# LPmini-Prototype_1_1.net
KiCad netlist of a schematic drawn in EAGLE
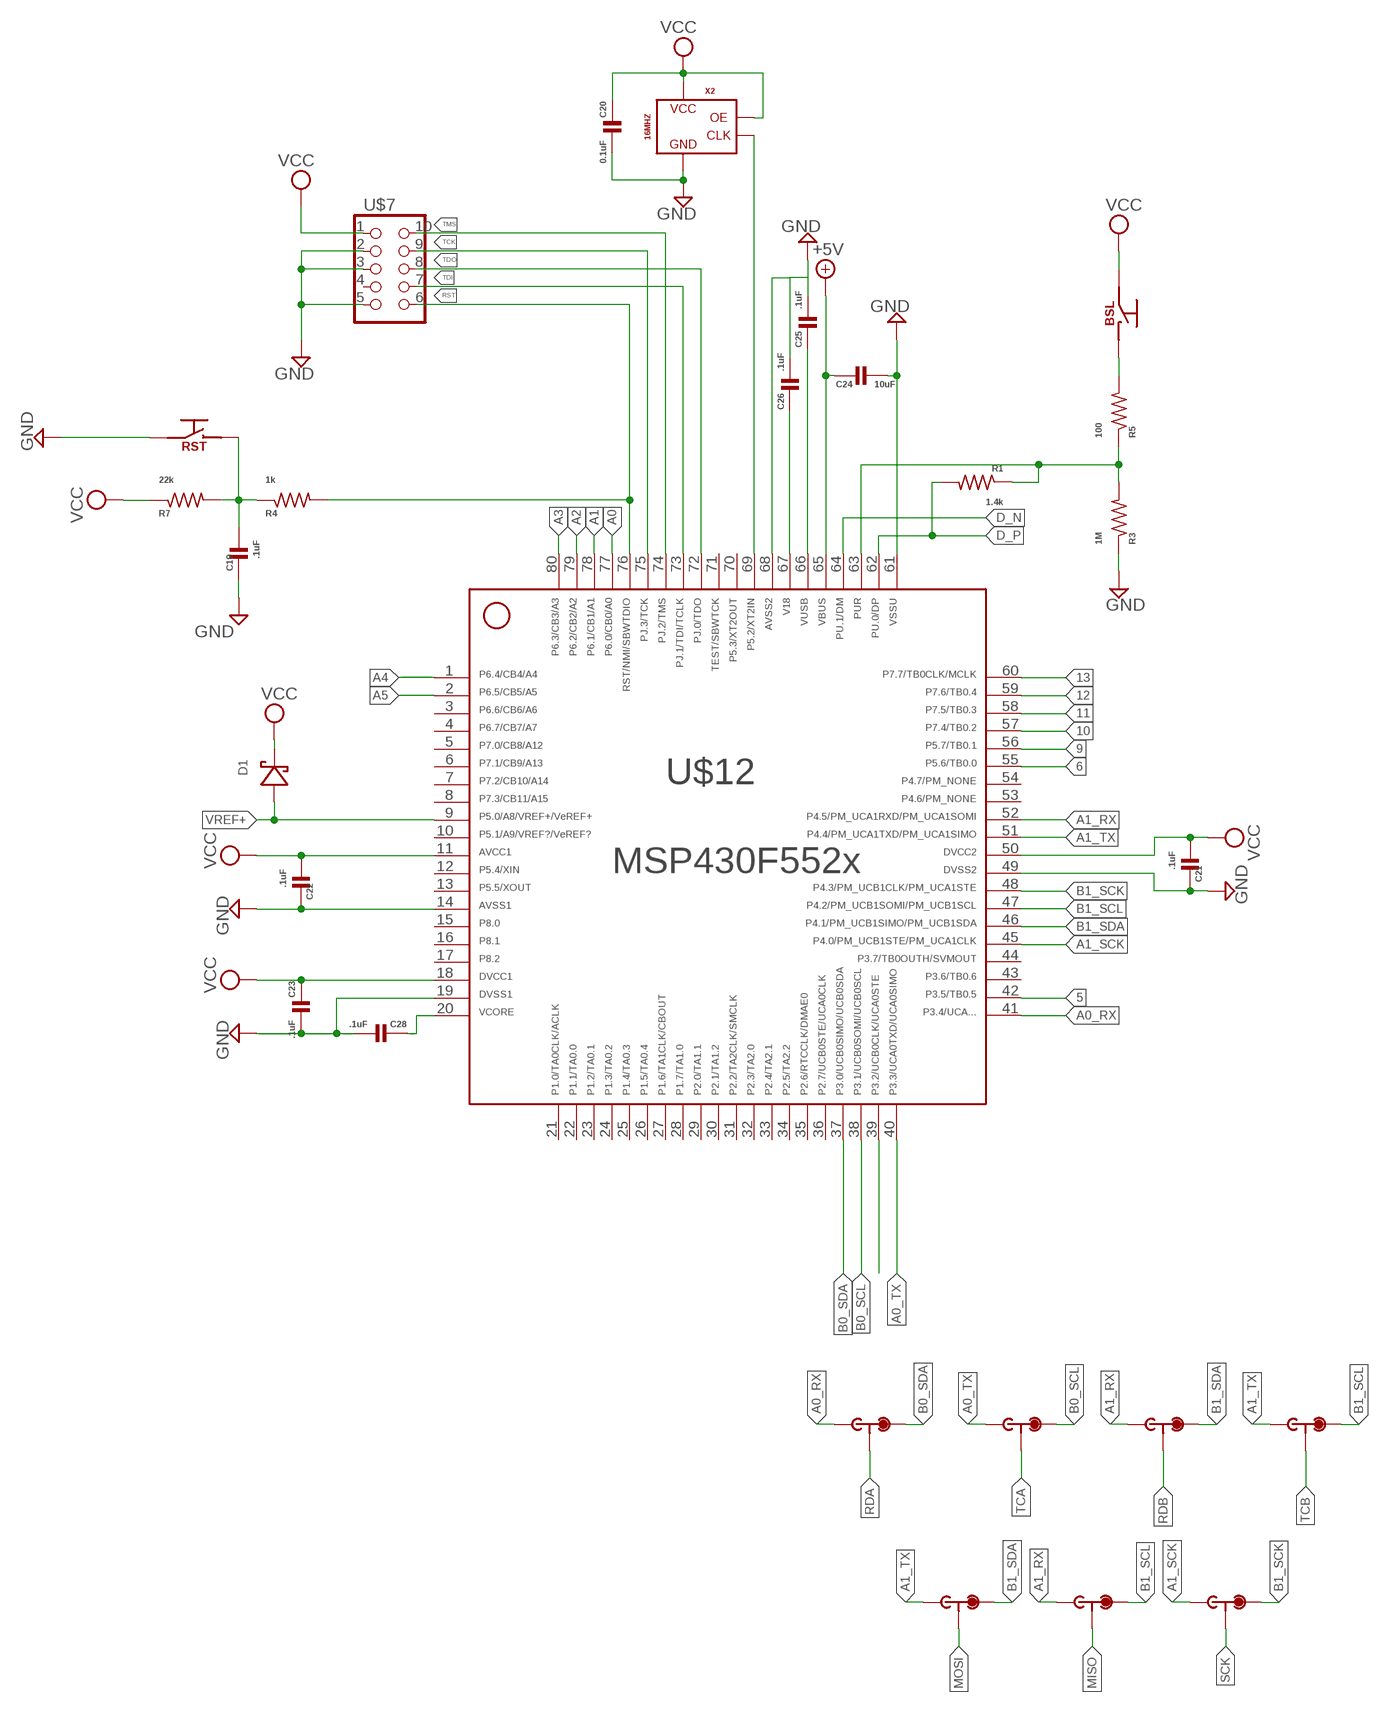
[diagram p0: schematic, sheet 1, part 1 of 2]
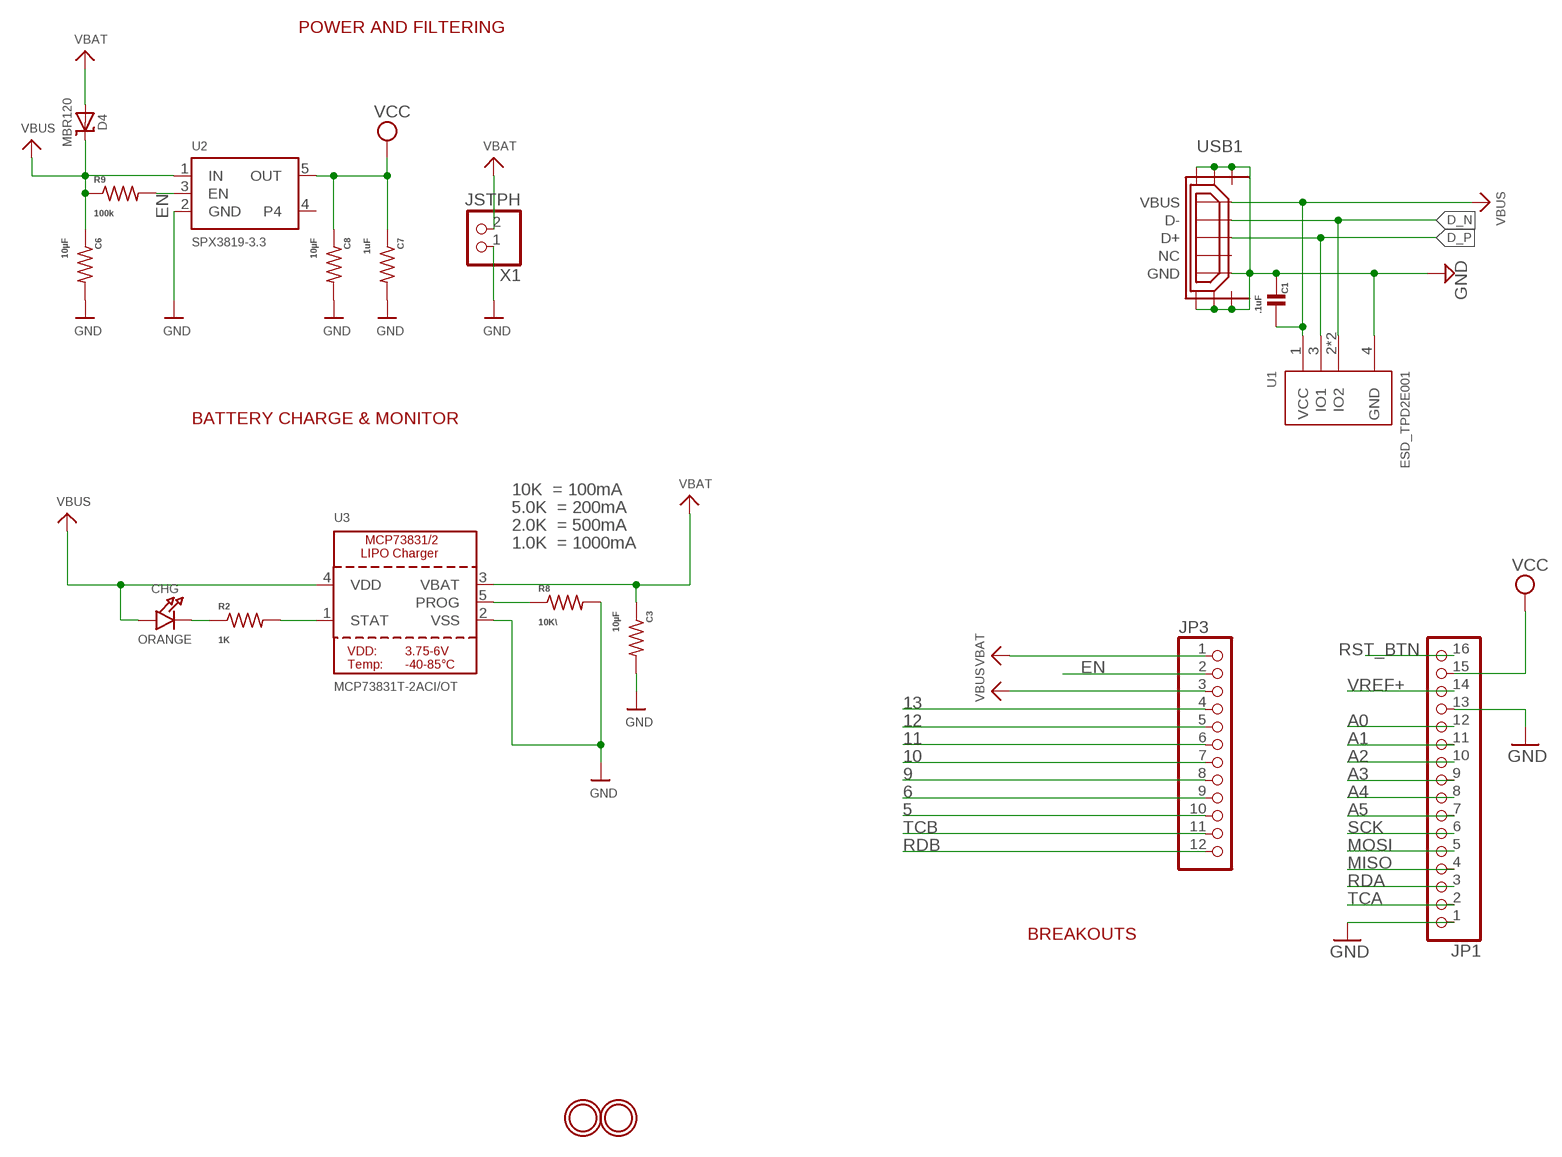
[diagram p1: schematic, sheet 1, part 2 of 2]

(export (version "E")
  (design (tool "Eeschema 10.0.6"))
  (components
    (comp (ref "BSL")
      (value "PB_SMALL_SMD")
      (footprint "eagle-import:PB_KMR2")
      (libsource (lib "eagle-import") (part "PB_SMALL_SMD"))
    )
    (comp (ref "C1")
      (value ".1uF")
      (footprint "eagle-import:C0402")
      (libsource (lib "eagle-import") (part "C-EUC0402"))
    )
    (comp (ref "C3")
      (value "10µF")
      (footprint "eagle-import:R0603")
      (libsource (lib "eagle-import") (part "R-US_R0603"))
    )
    (comp (ref "C6")
      (value "10µF")
      (footprint "eagle-import:R0603")
      (libsource (lib "eagle-import") (part "R-US_R0603"))
    )
    (comp (ref "C7")
      (value "1uF")
      (footprint "eagle-import:R0402")
      (libsource (lib "eagle-import") (part "R-US_R0402"))
    )
    (comp (ref "C8")
      (value "10µF")
      (footprint "eagle-import:R0603")
      (libsource (lib "eagle-import") (part "R-US_R0603"))
    )
    (comp (ref "C19")
      (value ".1uF")
      (footprint "eagle-import:C0402")
      (libsource (lib "eagle-import") (part "C-EUC0402"))
    )
    (comp (ref "C20")
      (value "0.1uF")
      (footprint "eagle-import:C0402")
      (libsource (lib "eagle-import") (part "C-EUC0402"))
    )
    (comp (ref "C21")
      (value ".1uF")
      (footprint "eagle-import:C0402")
      (libsource (lib "eagle-import") (part "C-EUC0402"))
    )
    (comp (ref "C22")
      (value ".1uF")
      (footprint "eagle-import:C0402")
      (libsource (lib "eagle-import") (part "C-EUC0402"))
    )
    (comp (ref "C23")
      (value ".1uF")
      (footprint "eagle-import:C0402")
      (libsource (lib "eagle-import") (part "C-EUC0402"))
    )
    (comp (ref "C24")
      (value "10uF")
      (footprint "eagle-import:C0603")
      (libsource (lib "eagle-import") (part "C-EUC0603"))
    )
    (comp (ref "C25")
      (value ".1uF")
      (footprint "eagle-import:C0402")
      (libsource (lib "eagle-import") (part "C-EUC0402"))
    )
    (comp (ref "C26")
      (value ".1uF")
      (footprint "eagle-import:C0402")
      (libsource (lib "eagle-import") (part "C-EUC0402"))
    )
    (comp (ref "C28")
      (value ".1uF")
      (footprint "eagle-import:C0402")
      (libsource (lib "eagle-import") (part "C-EUC0402"))
    )
    (comp (ref "CHG")
      (value "ORANGE")
      (footprint "eagle-import:CHIPLED_0805_NOOUTLINE")
      (libsource (lib "eagle-import") (part "LED0805_NOOUTLINE"))
    )
    (comp (ref "D1")
      (value "0_JOSEPH_SDIODE0603")
      (footprint "eagle-import:0_JOSEPH_D0603")
      (libsource (lib "eagle-import") (part "0_JOSEPH_SDIODE0603"))
    )
    (comp (ref "D4")
      (value "MBR120")
      (footprint "eagle-import:SOD-123")
      (libsource (lib "eagle-import") (part "DIODE-SCHOTTKYSOD-123"))
    )
    (comp (ref "JP1")
      (value "HEADER-1X16ROUND")
      (footprint "eagle-import:1X16_ROUND")
      (libsource (lib "eagle-import") (part "HEADER-1X16ROUND"))
    )
    (comp (ref "JP3")
      (value "HEADER-1X12")
      (footprint "eagle-import:1X12_ROUND")
      (libsource (lib "eagle-import") (part "HEADER-1X12"))
    )
    (comp (ref "R1")
      (value "1.4k")
      (footprint "eagle-import:R0402")
      (libsource (lib "eagle-import") (part "R-US_R0402"))
    )
    (comp (ref "R2")
      (value "1K")
      (footprint "eagle-import:R0402")
      (libsource (lib "eagle-import") (part "R-US_R0402"))
    )
    (comp (ref "R3")
      (value "1M")
      (footprint "eagle-import:R0402")
      (libsource (lib "eagle-import") (part "R-US_R0402"))
    )
    (comp (ref "R4")
      (value "1k")
      (footprint "eagle-import:R0402")
      (libsource (lib "eagle-import") (part "R-US_R0402"))
    )
    (comp (ref "R5")
      (value "100")
      (footprint "eagle-import:R0402")
      (libsource (lib "eagle-import") (part "R-US_R0402"))
    )
    (comp (ref "R7")
      (value "22k")
      (footprint "eagle-import:R0402")
      (libsource (lib "eagle-import") (part "R-US_R0402"))
    )
    (comp (ref "R8")
      (value "10K\\")
      (footprint "eagle-import:R0402")
      (libsource (lib "eagle-import") (part "R-US_R0402"))
    )
    (comp (ref "R9")
      (value "100k")
      (footprint "eagle-import:R0402")
      (libsource (lib "eagle-import") (part "R-US_R0402"))
    )
    (comp (ref "RST")
      (value "PB_SMALL_SMD")
      (footprint "eagle-import:PB_KMR2")
      (libsource (lib "eagle-import") (part "PB_SMALL_SMD"))
    )
    (comp (ref "U$2")
      (value "3PT_SOLDER_JUMPER")
      (footprint "eagle-import:SOLDER_JUMPER_3")
      (libsource (lib "eagle-import") (part "3PT_SOLDER_JUMPER"))
    )
    (comp (ref "U$4")
      (value "3PT_SOLDER_JUMPER")
      (footprint "eagle-import:SOLDER_JUMPER_3")
      (libsource (lib "eagle-import") (part "3PT_SOLDER_JUMPER"))
    )
    (comp (ref "U$5")
      (value "3PT_SOLDER_JUMPER")
      (footprint "eagle-import:SOLDER_JUMPER_3")
      (libsource (lib "eagle-import") (part "3PT_SOLDER_JUMPER"))
    )
    (comp (ref "U$6")
      (value "3PT_SOLDER_JUMPER")
      (footprint "eagle-import:SOLDER_JUMPER_3")
      (libsource (lib "eagle-import") (part "3PT_SOLDER_JUMPER"))
    )
    (comp (ref "U$7")
      (value "PINHD_2X05SMD")
      (footprint "eagle-import:2X05-SMALL_SMD")
      (libsource (lib "eagle-import") (part "PINHD_2X05SMD"))
    )
    (comp (ref "U$8")
      (value "3PT_SOLDER_JUMPER")
      (footprint "eagle-import:SOLDER_JUMPER_3")
      (libsource (lib "eagle-import") (part "3PT_SOLDER_JUMPER"))
    )
    (comp (ref "U$9")
      (value "3PT_SOLDER_JUMPER")
      (footprint "eagle-import:SOLDER_JUMPER_3")
      (libsource (lib "eagle-import") (part "3PT_SOLDER_JUMPER"))
    )
    (comp (ref "U$10")
      (value "3PT_SOLDER_JUMPER")
      (footprint "eagle-import:SOLDER_JUMPER_3")
      (libsource (lib "eagle-import") (part "3PT_SOLDER_JUMPER"))
    )
    (comp (ref "U$12")
      (value "TI_MSP430_V16_INTERN_F552X---PN80")
      (footprint "eagle-import:TI_MSP430_V16_INTERN_PN80")
      (libsource (lib "eagle-import") (part "TI_MSP430_V16_INTERN_F552X---PN80"))
    )
    (comp (ref "U$31")
      (value "MOUNTINGHOLE2.5")
      (footprint "eagle-import:MOUNTINGHOLE_2.5_PLATED")
      (libsource (lib "eagle-import") (part "MOUNTINGHOLE2.5"))
    )
    (comp (ref "U$32")
      (value "MOUNTINGHOLE2.5")
      (footprint "eagle-import:MOUNTINGHOLE_2.5_PLATED")
      (libsource (lib "eagle-import") (part "MOUNTINGHOLE2.5"))
    )
    (comp (ref "U1")
      (value "ESD_TPD2E001")
      (footprint "eagle-import:PROJECT7264_TPD2E001-DRL")
      (libsource (lib "eagle-import") (part "ESD_TPD2E001"))
    )
    (comp (ref "U2")
      (value "SPX3819-3.3")
      (footprint "eagle-import:SOT23-5")
      (libsource (lib "eagle-import") (part "VREG_SOT23-5"))
    )
    (comp (ref "U3")
      (value "MCP73831T-2ACI/OT")
      (footprint "eagle-import:SOT23-5")
      (libsource (lib "eagle-import") (part "MCP73831/2"))
    )
    (comp (ref "USB1")
      (value "USB_CON-UPDATE_USB_MICRO_FLIPPED")
      (footprint "eagle-import:USB_CON-UPDATE_HIROSE-ZX62R-B-5P")
      (libsource (lib "eagle-import") (part "USB_CON-UPDATE_USB_MICRO_FLIPPED"))
    )
    (comp (ref "X1")
      (value "JSTPH")
      (footprint "eagle-import:JSTPH2")
      (libsource (lib "eagle-import") (part "CON_JST_PH_2PIN"))
    )
    (comp (ref "X2")
      (value "16MHZ")
      (footprint "eagle-import:SMD_CRYSTAL_3.2X5_PERICOM")
      (libsource (lib "eagle-import") (part "OSCILLATOR_SMD_PERICOM"))
    )
  )
  (nets
    (net (code "1") (name "+5V") (class "Default")
      (node (ref "C24") (pin "1") (pinfunction "1_1") (pintype "passive"))
      (node (ref "U$12") (pin "65") (pinfunction "65_65") (pintype "power_in"))
    )
    (net (code "2") (name "/EN") (class "Default")
      (node (ref "JP3") (pin "2") (pinfunction "2_2") (pintype "passive"))
      (node (ref "R9") (pin "2") (pinfunction "2_2") (pintype "passive"))
      (node (ref "U2") (pin "3") (pinfunction "EN_3") (pintype "input"))
    )
    (net (code "3") (name "/RST_BTN") (class "Default")
      (node (ref "C19") (pin "1") (pinfunction "1_1") (pintype "passive"))
      (node (ref "JP1") (pin "16") (pinfunction "16_16") (pintype "passive"))
      (node (ref "R4") (pin "1") (pinfunction "1_1") (pintype "passive"))
      (node (ref "R7") (pin "2") (pinfunction "2_2") (pintype "passive"))
      (node (ref "RST") (pin "2A") (pinfunction "B_2A") (pintype "bidirectional"))
      (node (ref "RST") (pin "2B") (pinfunction "B_2B") (pintype "bidirectional"))
    )
    (net (code "4") (name "5") (class "Default")
      (node (ref "JP3") (pin "10") (pinfunction "10_10") (pintype "passive"))
      (node (ref "U$12") (pin "42") (pinfunction "42_42") (pintype "bidirectional"))
    )
    (net (code "5") (name "6") (class "Default")
      (node (ref "JP3") (pin "9") (pinfunction "9_9") (pintype "passive"))
      (node (ref "U$12") (pin "55") (pinfunction "55_55") (pintype "bidirectional"))
    )
    (net (code "6") (name "9") (class "Default")
      (node (ref "JP3") (pin "8") (pinfunction "8_8") (pintype "passive"))
      (node (ref "U$12") (pin "56") (pinfunction "56_56") (pintype "bidirectional"))
    )
    (net (code "7") (name "10") (class "Default")
      (node (ref "JP3") (pin "7") (pinfunction "7_7") (pintype "passive"))
      (node (ref "U$12") (pin "57") (pinfunction "57_57") (pintype "bidirectional"))
    )
    (net (code "8") (name "11") (class "Default")
      (node (ref "JP3") (pin "6") (pinfunction "6_6") (pintype "passive"))
      (node (ref "U$12") (pin "58") (pinfunction "58_58") (pintype "bidirectional"))
    )
    (net (code "9") (name "12") (class "Default")
      (node (ref "JP3") (pin "5") (pinfunction "5_5") (pintype "passive"))
      (node (ref "U$12") (pin "59") (pinfunction "59_59") (pintype "bidirectional"))
    )
    (net (code "10") (name "13") (class "Default")
      (node (ref "JP3") (pin "4") (pinfunction "4_4") (pintype "passive"))
      (node (ref "U$12") (pin "60") (pinfunction "60_60") (pintype "bidirectional"))
    )
    (net (code "11") (name "A0") (class "Default")
      (node (ref "JP1") (pin "12") (pinfunction "12_12") (pintype "passive"))
      (node (ref "U$12") (pin "77") (pinfunction "77_77") (pintype "bidirectional"))
    )
    (net (code "12") (name "A0_RX") (class "Default")
      (node (ref "U$12") (pin "41") (pinfunction "41_41") (pintype "bidirectional"))
      (node (ref "U$2") (pin "2") (pinfunction "NO_2") (pintype "bidirectional"))
    )
    (net (code "13") (name "A0_TX") (class "Default")
      (node (ref "U$12") (pin "40") (pinfunction "40_40") (pintype "bidirectional"))
      (node (ref "U$8") (pin "2") (pinfunction "NO_2") (pintype "bidirectional"))
    )
    (net (code "14") (name "A1") (class "Default")
      (node (ref "JP1") (pin "11") (pinfunction "11_11") (pintype "passive"))
      (node (ref "U$12") (pin "78") (pinfunction "78_78") (pintype "bidirectional"))
    )
    (net (code "15") (name "A1_RX") (class "Default")
      (node (ref "U$12") (pin "52") (pinfunction "52_52") (pintype "bidirectional"))
      (node (ref "U$5") (pin "2") (pinfunction "NO_2") (pintype "bidirectional"))
      (node (ref "U$9") (pin "2") (pinfunction "NO_2") (pintype "bidirectional"))
    )
    (net (code "16") (name "A1_SCK") (class "Default")
      (node (ref "U$12") (pin "45") (pinfunction "45_45") (pintype "bidirectional"))
      (node (ref "U$6") (pin "2") (pinfunction "NO_2") (pintype "bidirectional"))
    )
    (net (code "17") (name "A1_TX") (class "Default")
      (node (ref "U$10") (pin "2") (pinfunction "NO_2") (pintype "bidirectional"))
      (node (ref "U$12") (pin "51") (pinfunction "51_51") (pintype "bidirectional"))
      (node (ref "U$4") (pin "2") (pinfunction "NO_2") (pintype "bidirectional"))
    )
    (net (code "18") (name "A2") (class "Default")
      (node (ref "JP1") (pin "10") (pinfunction "10_10") (pintype "passive"))
      (node (ref "U$12") (pin "79") (pinfunction "79_79") (pintype "bidirectional"))
    )
    (net (code "19") (name "A3") (class "Default")
      (node (ref "JP1") (pin "9") (pinfunction "9_9") (pintype "passive"))
      (node (ref "U$12") (pin "80") (pinfunction "80_80") (pintype "bidirectional"))
    )
    (net (code "20") (name "A4") (class "Default")
      (node (ref "JP1") (pin "8") (pinfunction "8_8") (pintype "passive"))
      (node (ref "U$12") (pin "1") (pinfunction "1_1") (pintype "bidirectional"))
    )
    (net (code "21") (name "A5") (class "Default")
      (node (ref "JP1") (pin "7") (pinfunction "7_7") (pintype "passive"))
      (node (ref "U$12") (pin "2") (pinfunction "2_2") (pintype "bidirectional"))
    )
    (net (code "22") (name "B0_SCL") (class "Default")
      (node (ref "U$12") (pin "38") (pinfunction "38_38") (pintype "bidirectional"))
      (node (ref "U$8") (pin "1") (pinfunction "NC_1") (pintype "bidirectional"))
    )
    (net (code "23") (name "B0_SDA") (class "Default")
      (node (ref "U$12") (pin "37") (pinfunction "37_37") (pintype "bidirectional"))
      (node (ref "U$2") (pin "1") (pinfunction "NC_1") (pintype "bidirectional"))
    )
    (net (code "24") (name "B1_SCK") (class "Default")
      (node (ref "U$12") (pin "48") (pinfunction "48_48") (pintype "bidirectional"))
      (node (ref "U$6") (pin "1") (pinfunction "NC_1") (pintype "bidirectional"))
    )
    (net (code "25") (name "B1_SCL") (class "Default")
      (node (ref "U$10") (pin "1") (pinfunction "NC_1") (pintype "bidirectional"))
      (node (ref "U$12") (pin "47") (pinfunction "47_47") (pintype "bidirectional"))
      (node (ref "U$5") (pin "1") (pinfunction "NC_1") (pintype "bidirectional"))
    )
    (net (code "26") (name "B1_SDA") (class "Default")
      (node (ref "U$12") (pin "46") (pinfunction "46_46") (pintype "bidirectional"))
      (node (ref "U$4") (pin "1") (pinfunction "NC_1") (pintype "bidirectional"))
      (node (ref "U$9") (pin "1") (pinfunction "NC_1") (pintype "bidirectional"))
    )
    (net (code "27") (name "D_N") (class "Default")
      (node (ref "U$12") (pin "64") (pinfunction "64_64") (pintype "bidirectional"))
      (node (ref "U1") (pin "2") (pinfunction "IO2_2") (pintype "bidirectional"))
      (node (ref "U1") (pin "5") (pinfunction "IO2_5") (pintype "bidirectional"))
      (node (ref "USB1") (pin "D-") (pinfunction "D-_D-") (pintype "input"))
    )
    (net (code "28") (name "D_P") (class "Default")
      (node (ref "R1") (pin "2") (pinfunction "2_2") (pintype "passive"))
      (node (ref "U$12") (pin "62") (pinfunction "62_62") (pintype "bidirectional"))
      (node (ref "U1") (pin "3") (pinfunction "IO1_3") (pintype "bidirectional"))
      (node (ref "USB1") (pin "D+") (pinfunction "D+_D+") (pintype "input"))
    )
    (net (code "29") (name "GND") (class "Default")
      (node (ref "C1") (pin "2") (pinfunction "2_2") (pintype "passive"))
      (node (ref "C19") (pin "2") (pinfunction "2_2") (pintype "passive"))
      (node (ref "C20") (pin "2") (pinfunction "2_2") (pintype "passive"))
      (node (ref "C21") (pin "2") (pinfunction "2_2") (pintype "passive"))
      (node (ref "C22") (pin "2") (pinfunction "2_2") (pintype "passive"))
      (node (ref "C23") (pin "2") (pinfunction "2_2") (pintype "passive"))
      (node (ref "C24") (pin "2") (pinfunction "2_2") (pintype "passive"))
      (node (ref "C25") (pin "2") (pinfunction "2_2") (pintype "passive"))
      (node (ref "C26") (pin "2") (pinfunction "2_2") (pintype "passive"))
      (node (ref "C28") (pin "2") (pinfunction "2_2") (pintype "passive"))
      (node (ref "C3") (pin "2") (pinfunction "2_2") (pintype "passive"))
      (node (ref "C6") (pin "2") (pinfunction "2_2") (pintype "passive"))
      (node (ref "C7") (pin "2") (pinfunction "2_2") (pintype "passive"))
      (node (ref "C8") (pin "2") (pinfunction "2_2") (pintype "passive"))
      (node (ref "JP1") (pin "1") (pinfunction "1_1") (pintype "passive"))
      (node (ref "JP1") (pin "13") (pinfunction "13_13") (pintype "passive"))
      (node (ref "R3") (pin "1") (pinfunction "1_1") (pintype "passive"))
      (node (ref "R8") (pin "2") (pinfunction "2_2") (pintype "passive"))
      (node (ref "RST") (pin "1A") (pinfunction "A_1A") (pintype "bidirectional"))
      (node (ref "RST") (pin "1B") (pinfunction "A_1B") (pintype "bidirectional"))
      (node (ref "U$12") (pin "14") (pinfunction "14_14") (pintype "power_in"))
      (node (ref "U$12") (pin "19") (pinfunction "19_19") (pintype "power_in"))
      (node (ref "U$12") (pin "49") (pinfunction "49_49") (pintype "power_in"))
      (node (ref "U$12") (pin "61") (pinfunction "61_61") (pintype "power_in"))
      (node (ref "U$12") (pin "68") (pinfunction "68_68") (pintype "power_in"))
      (node (ref "U$7") (pin "2") (pinfunction "2_2") (pintype "passive"))
      (node (ref "U$7") (pin "3") (pinfunction "3_3") (pintype "passive"))
      (node (ref "U$7") (pin "5") (pinfunction "5_5") (pintype "passive"))
      (node (ref "U1") (pin "4") (pinfunction "GND_4") (pintype "power_in"))
      (node (ref "U2") (pin "2") (pinfunction "GND_2") (pintype "power_in"))
      (node (ref "U3") (pin "2") (pinfunction "VSS_2") (pintype "power_in"))
      (node (ref "USB1") (pin "GND") (pinfunction "GND_GND") (pintype "input"))
      (node (ref "USB1") (pin "SHIELD1") (pinfunction "SHIELD1_SHIELD1") (pintype "bidirectional"))
      (node (ref "USB1") (pin "SHIELD2") (pinfunction "SHIELD2_SHIELD2") (pintype "bidirectional"))
      (node (ref "USB1") (pin "SHIELD3") (pinfunction "SHIELD3_SHIELD3") (pintype "bidirectional"))
      (node (ref "USB1") (pin "SHIELD4") (pinfunction "SHIELD4_SHIELD4") (pintype "bidirectional"))
      (node (ref "USB1") (pin "SHIELD5") (pinfunction "SHIELD5_SHIELD5") (pintype "bidirectional"))
      (node (ref "USB1") (pin "SHIELD6") (pinfunction "SHIELD6_SHIELD6") (pintype "bidirectional"))
      (node (ref "X1") (pin "1") (pinfunction "1_1") (pintype "passive"))
      (node (ref "X2") (pin "2") (pinfunction "2_2") (pintype "bidirectional"))
    )
    (net (code "30") (name "MISO") (class "Default")
      (node (ref "JP1") (pin "4") (pinfunction "4_4") (pintype "passive"))
      (node (ref "U$5") (pin "C") (pinfunction "IN_C") (pintype "bidirectional"))
    )
    (net (code "31") (name "MOSI") (class "Default")
      (node (ref "JP1") (pin "5") (pinfunction "5_5") (pintype "passive"))
      (node (ref "U$4") (pin "C") (pinfunction "IN_C") (pintype "bidirectional"))
    )
    (net (code "32") (name "Net-(BSL-B-Pad2A)") (class "Default")
      (node (ref "BSL") (pin "2A") (pinfunction "B_2A") (pintype "bidirectional"))
      (node (ref "BSL") (pin "2B") (pinfunction "B_2B") (pintype "bidirectional"))
      (node (ref "R5") (pin "2") (pinfunction "2_2") (pintype "passive"))
    )
    (net (code "33") (name "Net-(C25-Pad1)") (class "Default")
      (node (ref "C25") (pin "1") (pinfunction "1_1") (pintype "passive"))
      (node (ref "U$12") (pin "66") (pinfunction "66_66") (pintype "power_in"))
    )
    (net (code "34") (name "Net-(C26-Pad1)") (class "Default")
      (node (ref "C26") (pin "1") (pinfunction "1_1") (pintype "passive"))
      (node (ref "U$12") (pin "67") (pinfunction "67_67") (pintype "power_in"))
    )
    (net (code "35") (name "Net-(C28-Pad1)") (class "Default")
      (node (ref "C28") (pin "1") (pinfunction "1_1") (pintype "passive"))
      (node (ref "U$12") (pin "20") (pinfunction "20_20") (pintype "power_in"))
    )
    (net (code "36") (name "Net-(CHG-PadC)") (class "Default")
      (node (ref "CHG") (pin "C") (pinfunction "C_C") (pintype "passive"))
      (node (ref "R2") (pin "1") (pinfunction "1_1") (pintype "passive"))
    )
    (net (code "37") (name "Net-(R1-Pad1)") (class "Default")
      (node (ref "R1") (pin "1") (pinfunction "1_1") (pintype "passive"))
      (node (ref "R3") (pin "2") (pinfunction "2_2") (pintype "passive"))
      (node (ref "R5") (pin "1") (pinfunction "1_1") (pintype "passive"))
      (node (ref "U$12") (pin "63") (pinfunction "63_63") (pintype "bidirectional"))
    )
    (net (code "38") (name "Net-(U$12-Pad69)") (class "Default")
      (node (ref "U$12") (pin "69") (pinfunction "69_69") (pintype "bidirectional"))
      (node (ref "X2") (pin "3") (pinfunction "3_3") (pintype "bidirectional"))
    )
    (net (code "39") (name "Net-(U3-PROG)") (class "Default")
      (node (ref "R8") (pin "1") (pinfunction "1_1") (pintype "passive"))
      (node (ref "U3") (pin "5") (pinfunction "PROG_5") (pintype "input"))
    )
    (net (code "40") (name "Net-(U3-STAT)") (class "Default")
      (node (ref "R2") (pin "2") (pinfunction "2_2") (pintype "passive"))
      (node (ref "U3") (pin "1") (pinfunction "STAT_1") (pintype "output"))
    )
    (net (code "41") (name "RDA") (class "Default")
      (node (ref "JP1") (pin "3") (pinfunction "3_3") (pintype "passive"))
      (node (ref "U$2") (pin "C") (pinfunction "IN_C") (pintype "bidirectional"))
    )
    (net (code "42") (name "RDB") (class "Default")
      (node (ref "JP3") (pin "12") (pinfunction "12_12") (pintype "passive"))
      (node (ref "U$9") (pin "C") (pinfunction "IN_C") (pintype "bidirectional"))
    )
    (net (code "43") (name "RST") (class "Default")
      (node (ref "R4") (pin "2") (pinfunction "2_2") (pintype "passive"))
      (node (ref "U$12") (pin "76") (pinfunction "76_76") (pintype "bidirectional"))
      (node (ref "U$7") (pin "6") (pinfunction "6_6") (pintype "passive"))
    )
    (net (code "44") (name "SCK") (class "Default")
      (node (ref "JP1") (pin "6") (pinfunction "6_6") (pintype "passive"))
      (node (ref "U$6") (pin "C") (pinfunction "IN_C") (pintype "bidirectional"))
    )
    (net (code "45") (name "TCA") (class "Default")
      (node (ref "JP1") (pin "2") (pinfunction "2_2") (pintype "passive"))
      (node (ref "U$8") (pin "C") (pinfunction "IN_C") (pintype "bidirectional"))
    )
    (net (code "46") (name "TCB") (class "Default")
      (node (ref "JP3") (pin "11") (pinfunction "11_11") (pintype "passive"))
      (node (ref "U$10") (pin "C") (pinfunction "IN_C") (pintype "bidirectional"))
    )
    (net (code "47") (name "TCK") (class "Default")
      (node (ref "U$12") (pin "75") (pinfunction "75_75") (pintype "bidirectional"))
      (node (ref "U$7") (pin "9") (pinfunction "9_9") (pintype "passive"))
    )
    (net (code "48") (name "TDI") (class "Default")
      (node (ref "U$12") (pin "73") (pinfunction "73_73") (pintype "bidirectional"))
      (node (ref "U$7") (pin "7") (pinfunction "7_7") (pintype "passive"))
    )
    (net (code "49") (name "TDO") (class "Default")
      (node (ref "U$12") (pin "72") (pinfunction "72_72") (pintype "bidirectional"))
      (node (ref "U$7") (pin "8") (pinfunction "8_8") (pintype "passive"))
    )
    (net (code "50") (name "TMS") (class "Default")
      (node (ref "U$12") (pin "74") (pinfunction "74_74") (pintype "bidirectional"))
      (node (ref "U$7") (pin "10") (pinfunction "10_10") (pintype "passive"))
    )
    (net (code "51") (name "VBAT") (class "Default")
      (node (ref "C3") (pin "1") (pinfunction "1_1") (pintype "passive"))
      (node (ref "D4") (pin "A") (pinfunction "A_A") (pintype "passive"))
      (node (ref "JP3") (pin "1") (pinfunction "1_1") (pintype "passive"))
      (node (ref "U3") (pin "3") (pinfunction "VBAT_3") (pintype "power_in"))
      (node (ref "X1") (pin "2") (pinfunction "2_2") (pintype "passive"))
    )
    (net (code "52") (name "VBUS") (class "Default")
      (node (ref "C1") (pin "1") (pinfunction "1_1") (pintype "passive"))
      (node (ref "C6") (pin "1") (pinfunction "1_1") (pintype "passive"))
      (node (ref "CHG") (pin "A") (pinfunction "A_A") (pintype "passive"))
      (node (ref "D4") (pin "C") (pinfunction "C_C") (pintype "passive"))
      (node (ref "JP3") (pin "3") (pinfunction "3_3") (pintype "passive"))
      (node (ref "R9") (pin "1") (pinfunction "1_1") (pintype "passive"))
      (node (ref "U1") (pin "1") (pinfunction "VCC_1") (pintype "power_in"))
      (node (ref "U2") (pin "1") (pinfunction "IN_1") (pintype "power_in"))
      (node (ref "U3") (pin "4") (pinfunction "VDD_4") (pintype "power_in"))
      (node (ref "USB1") (pin "VBUS") (pinfunction "VBUS_VBUS") (pintype "input"))
    )
    (net (code "53") (name "VCC") (class "Default")
      (node (ref "BSL") (pin "1A") (pinfunction "A_1A") (pintype "bidirectional"))
      (node (ref "BSL") (pin "1B") (pinfunction "A_1B") (pintype "bidirectional"))
      (node (ref "C20") (pin "1") (pinfunction "1_1") (pintype "passive"))
      (node (ref "C21") (pin "1") (pinfunction "1_1") (pintype "passive"))
      (node (ref "C22") (pin "1") (pinfunction "1_1") (pintype "passive"))
      (node (ref "C23") (pin "1") (pinfunction "1_1") (pintype "passive"))
      (node (ref "C7") (pin "1") (pinfunction "1_1") (pintype "passive"))
      (node (ref "C8") (pin "1") (pinfunction "1_1") (pintype "passive"))
      (node (ref "D1") (pin "CA") (pinfunction "CA_CA") (pintype "bidirectional"))
      (node (ref "JP1") (pin "15") (pinfunction "15_15") (pintype "passive"))
      (node (ref "R7") (pin "1") (pinfunction "1_1") (pintype "passive"))
      (node (ref "U$12") (pin "11") (pinfunction "11_11") (pintype "power_in"))
      (node (ref "U$12") (pin "18") (pinfunction "18_18") (pintype "power_in"))
      (node (ref "U$12") (pin "50") (pinfunction "50_50") (pintype "power_in"))
      (node (ref "U$7") (pin "1") (pinfunction "1_1") (pintype "passive"))
      (node (ref "U2") (pin "5") (pinfunction "OUT_5") (pintype "power_in"))
      (node (ref "X2") (pin "1") (pinfunction "1_1") (pintype "bidirectional"))
      (node (ref "X2") (pin "4") (pinfunction "4_4") (pintype "bidirectional"))
    )
    (net (code "54") (name "VREF+") (class "Default")
      (node (ref "D1") (pin "AN") (pinfunction "AN_AN") (pintype "bidirectional"))
      (node (ref "JP1") (pin "14") (pinfunction "14_14") (pintype "passive"))
      (node (ref "U$12") (pin "9") (pinfunction "9_9") (pintype "bidirectional"))
    )
    (net (code "55") (name "unconnected-(U$7-Pad4)") (class "Default")
      (node (ref "U$7") (pin "4") (pinfunction "4_4") (pintype "passive"))
    )
    (net (code "56") (name "unconnected-(U$12-Pad3)") (class "Default")
      (node (ref "U$12") (pin "3") (pinfunction "3_3") (pintype "bidirectional"))
    )
    (net (code "57") (name "unconnected-(U$12-Pad4)") (class "Default")
      (node (ref "U$12") (pin "4") (pinfunction "4_4") (pintype "bidirectional"))
    )
    (net (code "58") (name "unconnected-(U$12-Pad5)") (class "Default")
      (node (ref "U$12") (pin "5") (pinfunction "5_5") (pintype "bidirectional"))
    )
    (net (code "59") (name "unconnected-(U$12-Pad6)") (class "Default")
      (node (ref "U$12") (pin "6") (pinfunction "6_6") (pintype "bidirectional"))
    )
    (net (code "60") (name "unconnected-(U$12-Pad7)") (class "Default")
      (node (ref "U$12") (pin "7") (pinfunction "7_7") (pintype "bidirectional"))
    )
    (net (code "61") (name "unconnected-(U$12-Pad8)") (class "Default")
      (node (ref "U$12") (pin "8") (pinfunction "8_8") (pintype "bidirectional"))
    )
    (net (code "62") (name "unconnected-(U$12-Pad10)") (class "Default")
      (node (ref "U$12") (pin "10") (pinfunction "10_10") (pintype "bidirectional"))
    )
    (net (code "63") (name "unconnected-(U$12-Pad12)") (class "Default")
      (node (ref "U$12") (pin "12") (pinfunction "12_12") (pintype "bidirectional"))
    )
    (net (code "64") (name "unconnected-(U$12-Pad13)") (class "Default")
      (node (ref "U$12") (pin "13") (pinfunction "13_13") (pintype "bidirectional"))
    )
    (net (code "65") (name "unconnected-(U$12-Pad15)") (class "Default")
      (node (ref "U$12") (pin "15") (pinfunction "15_15") (pintype "bidirectional"))
    )
    (net (code "66") (name "unconnected-(U$12-Pad16)") (class "Default")
      (node (ref "U$12") (pin "16") (pinfunction "16_16") (pintype "bidirectional"))
    )
    (net (code "67") (name "unconnected-(U$12-Pad17)") (class "Default")
      (node (ref "U$12") (pin "17") (pinfunction "17_17") (pintype "bidirectional"))
    )
    (net (code "68") (name "unconnected-(U$12-Pad21)") (class "Default")
      (node (ref "U$12") (pin "21") (pinfunction "21_21") (pintype "bidirectional"))
    )
    (net (code "69") (name "unconnected-(U$12-Pad22)") (class "Default")
      (node (ref "U$12") (pin "22") (pinfunction "22_22") (pintype "bidirectional"))
    )
    (net (code "70") (name "unconnected-(U$12-Pad23)") (class "Default")
      (node (ref "U$12") (pin "23") (pinfunction "23_23") (pintype "bidirectional"))
    )
    (net (code "71") (name "unconnected-(U$12-Pad24)") (class "Default")
      (node (ref "U$12") (pin "24") (pinfunction "24_24") (pintype "bidirectional"))
    )
    (net (code "72") (name "unconnected-(U$12-Pad25)") (class "Default")
      (node (ref "U$12") (pin "25") (pinfunction "25_25") (pintype "bidirectional"))
    )
    (net (code "73") (name "unconnected-(U$12-Pad26)") (class "Default")
      (node (ref "U$12") (pin "26") (pinfunction "26_26") (pintype "bidirectional"))
    )
    (net (code "74") (name "unconnected-(U$12-Pad27)") (class "Default")
      (node (ref "U$12") (pin "27") (pinfunction "27_27") (pintype "bidirectional"))
    )
    (net (code "75") (name "unconnected-(U$12-Pad28)") (class "Default")
      (node (ref "U$12") (pin "28") (pinfunction "28_28") (pintype "bidirectional"))
    )
    (net (code "76") (name "unconnected-(U$12-Pad29)") (class "Default")
      (node (ref "U$12") (pin "29") (pinfunction "29_29") (pintype "bidirectional"))
    )
    (net (code "77") (name "unconnected-(U$12-Pad30)") (class "Default")
      (node (ref "U$12") (pin "30") (pinfunction "30_30") (pintype "bidirectional"))
    )
    (net (code "78") (name "unconnected-(U$12-Pad31)") (class "Default")
      (node (ref "U$12") (pin "31") (pinfunction "31_31") (pintype "bidirectional"))
    )
    (net (code "79") (name "unconnected-(U$12-Pad32)") (class "Default")
      (node (ref "U$12") (pin "32") (pinfunction "32_32") (pintype "bidirectional"))
    )
    (net (code "80") (name "unconnected-(U$12-Pad33)") (class "Default")
      (node (ref "U$12") (pin "33") (pinfunction "33_33") (pintype "bidirectional"))
    )
    (net (code "81") (name "unconnected-(U$12-Pad34)") (class "Default")
      (node (ref "U$12") (pin "34") (pinfunction "34_34") (pintype "bidirectional"))
    )
    (net (code "82") (name "unconnected-(U$12-Pad35)") (class "Default")
      (node (ref "U$12") (pin "35") (pinfunction "35_35") (pintype "bidirectional"))
    )
    (net (code "83") (name "unconnected-(U$12-Pad36)") (class "Default")
      (node (ref "U$12") (pin "36") (pinfunction "36_36") (pintype "bidirectional"))
    )
    (net (code "84") (name "unconnected-(U$12-Pad39)") (class "Default")
      (node (ref "U$12") (pin "39") (pinfunction "39_39") (pintype "bidirectional"))
    )
    (net (code "85") (name "unconnected-(U$12-Pad43)") (class "Default")
      (node (ref "U$12") (pin "43") (pinfunction "43_43") (pintype "bidirectional"))
    )
    (net (code "86") (name "unconnected-(U$12-Pad44)") (class "Default")
      (node (ref "U$12") (pin "44") (pinfunction "44_44") (pintype "bidirectional"))
    )
    (net (code "87") (name "unconnected-(U$12-Pad53)") (class "Default")
      (node (ref "U$12") (pin "53") (pinfunction "53_53") (pintype "bidirectional"))
    )
    (net (code "88") (name "unconnected-(U$12-Pad54)") (class "Default")
      (node (ref "U$12") (pin "54") (pinfunction "54_54") (pintype "bidirectional"))
    )
    (net (code "89") (name "unconnected-(U$12-Pad70)") (class "Default")
      (node (ref "U$12") (pin "70") (pinfunction "70_70") (pintype "bidirectional"))
    )
    (net (code "90") (name "unconnected-(U$12-Pad71)") (class "Default")
      (node (ref "U$12") (pin "71") (pinfunction "71_71") (pintype "input"))
    )
    (net (code "91") (name "unconnected-(U2-P4-Pad4)") (class "Default")
      (node (ref "U2") (pin "4") (pinfunction "P4_4") (pintype "bidirectional"))
    )
    (net (code "92") (name "unconnected-(USB1-PadNC)") (class "Default")
      (node (ref "USB1") (pin "NC") (pinfunction "NC_NC") (pintype "input"))
    )
  )
)
